# protect.net
KiCad netlist of a schematic drawn in Altium Designer
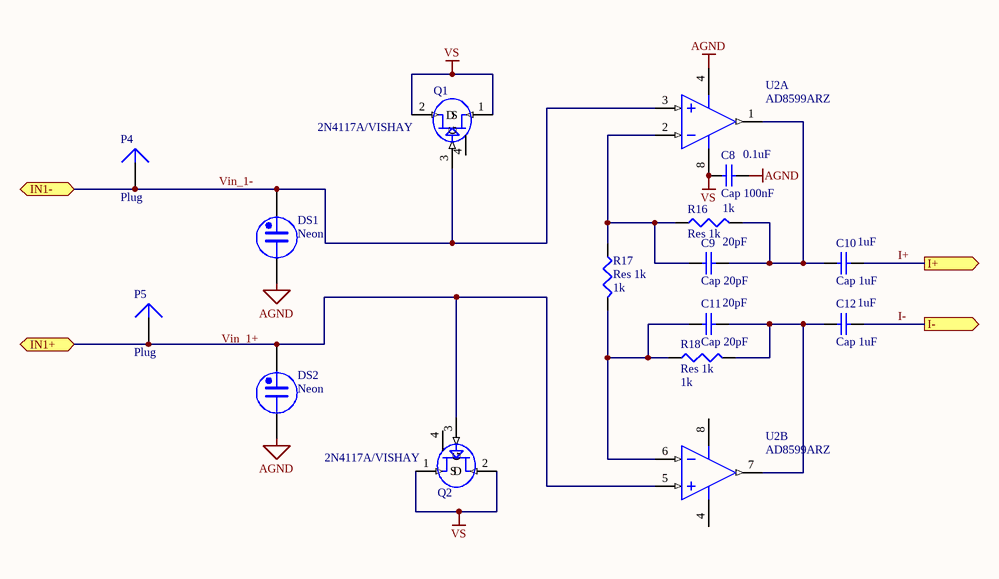
[diagram p0: protect.SchDoc]

(export (version "E")
  (design (tool "Eeschema 10.0.6"))
  (components
    (comp (ref "C8")
      (value "Cap 100nF")
      (footprint "0402")
      (description "Capacitor (Semiconductor SIM Model)")
      (fields (field (name "ALTIUM_VALUE") "0.1uF") (field (name "PUBLISHER") "Altium Limited"))
      (libsource (lib "Miscellaneous Devices") (part "Cap Semi"))
    )
    (comp (ref "C9")
      (value "Cap 20pF")
      (footprint "0402")
      (description "Capacitor (Semiconductor SIM Model)")
      (fields (field (name "ALTIUM_VALUE") "20pF") (field (name "PUBLISHER") "Altium Limited"))
      (libsource (lib "Miscellaneous Devices") (part "Cap Semi"))
    )
    (comp (ref "C10")
      (value "Cap 1uF")
      (footprint "0402")
      (description "Capacitor (Semiconductor SIM Model)")
      (fields (field (name "ALTIUM_VALUE") "1uF") (field (name "PUBLISHER") "Altium Limited"))
      (libsource (lib "Miscellaneous Devices") (part "Cap Semi"))
    )
    (comp (ref "C11")
      (value "Cap 20pF")
      (footprint "0402")
      (description "Capacitor (Semiconductor SIM Model)")
      (fields (field (name "ALTIUM_VALUE") "20pF") (field (name "PUBLISHER") "Altium Limited"))
      (libsource (lib "Miscellaneous Devices") (part "Cap Semi"))
    )
    (comp (ref "C12")
      (value "Cap 1uF")
      (footprint "0402")
      (description "Capacitor (Semiconductor SIM Model)")
      (fields (field (name "ALTIUM_VALUE") "1uF") (field (name "PUBLISHER") "Altium Limited"))
      (libsource (lib "Miscellaneous Devices") (part "Cap Semi"))
    )
    (comp (ref "DS1")
      (value "Neon")
      (footprint "PIN2")
      (description "Neon Bulb")
      (fields (field (name "PUBLISHER") "Altium Limited"))
      (libsource (lib "Miscellaneous Devices") (part "Neon"))
    )
    (comp (ref "DS2")
      (value "Neon")
      (footprint "PIN2")
      (description "Neon Bulb")
      (fields (field (name "PUBLISHER") "Altium Limited"))
      (libsource (lib "Miscellaneous Devices") (part "Neon"))
    )
    (comp (ref "P4")
      (value "Plug")
      (footprint "PIN1")
      (fields (field (name "PUBLISHER") "Altium Limited"))
      (libsource (lib "Miscellaneous Connectors") (part "Plug"))
    )
    (comp (ref "P5")
      (value "Plug")
      (footprint "PIN1")
      (fields (field (name "PUBLISHER") "Altium Limited"))
      (libsource (lib "Miscellaneous Connectors") (part "Plug"))
    )
    (comp (ref "Q1") (value "2N4117A/VISHAY") (footprint "TO236") (libsource (lib "*") (part "JFET N")))
    (comp (ref "Q2") (value "2N4117A/VISHAY") (footprint "TO236") (libsource (lib "*") (part "JFET N")))
    (comp (ref "R16")
      (value "Res 1k")
      (footprint "0402")
      (description "Resistor")
      (fields (field (name "ALTIUM_VALUE") "1k") (field (name "PUBLISHER") "Altium Limited"))
      (libsource (lib "Miscellaneous Devices") (part "Res3"))
    )
    (comp (ref "R17")
      (value "Res 1k")
      (footprint "0402")
      (description "Resistor")
      (fields (field (name "ALTIUM_VALUE") "1k") (field (name "PUBLISHER") "Altium Limited"))
      (libsource (lib "Miscellaneous Devices") (part "Res3"))
    )
    (comp (ref "R18")
      (value "Res 1k")
      (footprint "0402")
      (description "Resistor")
      (fields (field (name "ALTIUM_VALUE") "1k") (field (name "PUBLISHER") "Altium Limited"))
      (libsource (lib "Miscellaneous Devices") (part "Res3"))
    )
    (comp (ref "U2")
      (value "AD8599ARZ")
      (footprint "ADI-R-8_N")
      (fields (field (name "GENERICA PART NUMBER") "AD8599") (field (name "MANUFACTURER") "Analog Devices"))
      (libsource (lib "Analog Devices Operational Amplifiers") (part "AD8599ARZ"))
    )
  )
  (nets
    (net (code "1") (name "/I+") (class "Default")
      (node (ref "C10") (pin "1") (pinfunction "1_1") (pintype "passive"))
    )
    (net (code "2") (name "/I-") (class "Default")
      (node (ref "C12") (pin "1") (pinfunction "1_1") (pintype "passive"))
    )
    (net (code "3") (name "/IN1+") (class "Default")
      (node (ref "DS2") (pin "1") (pinfunction "1_1") (pintype "passive"))
      (node (ref "P5") (pin "1") (pinfunction "1_1") (pintype "passive"))
      (node (ref "Q2") (pin "3") (pinfunction "G_3") (pintype "input"))
      (node (ref "U2") (pin "5") (pinfunction "+IN_B_5") (pintype "input"))
    )
    (net (code "5") (name "/Vin_1-") (class "Default")
      (node (ref "DS1") (pin "1") (pinfunction "1_1") (pintype "passive"))
      (node (ref "P4") (pin "1") (pinfunction "1_1") (pintype "passive"))
      (node (ref "Q1") (pin "3") (pinfunction "G_3") (pintype "input"))
      (node (ref "U2") (pin "3") (pinfunction "+IN_A_3") (pintype "input"))
    )
    (net (code "6") (name "AGND") (class "Default")
      (node (ref "C8") (pin "1") (pinfunction "1_1") (pintype "passive"))
      (node (ref "DS1") (pin "2") (pinfunction "2_2") (pintype "passive"))
      (node (ref "DS2") (pin "2") (pinfunction "2_2") (pintype "passive"))
      (node (ref "U2") (pin "4") (pinfunction "-V_4") (pintype "power_in"))
    )
    (net (code "7") (name "Net-(U2A--IN_A)") (class "Default")
      (node (ref "C9") (pin "2") (pinfunction "2_2") (pintype "passive"))
      (node (ref "R16") (pin "1") (pinfunction "1_1") (pintype "passive"))
      (node (ref "R17") (pin "1") (pinfunction "1_1") (pintype "passive"))
      (node (ref "U2") (pin "2") (pinfunction "-IN_A_2") (pintype "input"))
    )
    (net (code "8") (name "Net-(U2A-OUT_A)") (class "Default")
      (node (ref "C10") (pin "2") (pinfunction "2_2") (pintype "passive"))
      (node (ref "C9") (pin "1") (pinfunction "1_1") (pintype "passive"))
      (node (ref "R16") (pin "2") (pinfunction "2_2") (pintype "passive"))
      (node (ref "U2") (pin "1") (pinfunction "OUT_A_1") (pintype "output"))
    )
    (net (code "9") (name "Net-(U2B--IN_B)") (class "Default")
      (node (ref "C11") (pin "2") (pinfunction "2_2") (pintype "passive"))
      (node (ref "R17") (pin "2") (pinfunction "2_2") (pintype "passive"))
      (node (ref "R18") (pin "1") (pinfunction "1_1") (pintype "passive"))
      (node (ref "U2") (pin "6") (pinfunction "-IN_B_6") (pintype "input"))
    )
    (net (code "10") (name "Net-(U2B-OUT_B)") (class "Default")
      (node (ref "C11") (pin "1") (pinfunction "1_1") (pintype "passive"))
      (node (ref "C12") (pin "2") (pinfunction "2_2") (pintype "passive"))
      (node (ref "R18") (pin "2") (pinfunction "2_2") (pintype "passive"))
      (node (ref "U2") (pin "7") (pinfunction "OUT_B_7") (pintype "output"))
    )
    (net (code "11") (name "VS") (class "Default")
      (node (ref "C8") (pin "2") (pinfunction "2_2") (pintype "passive"))
      (node (ref "Q1") (pin "1") (pinfunction "S_1") (pintype "input"))
      (node (ref "Q1") (pin "2") (pinfunction "D_2") (pintype "input"))
      (node (ref "Q2") (pin "1") (pinfunction "S_1") (pintype "input"))
      (node (ref "Q2") (pin "2") (pinfunction "D_2") (pintype "input"))
      (node (ref "U2") (pin "8") (pinfunction "+V_8") (pintype "power_in"))
    )
    (net (code "12") (name "unconnected-(Q1-Pad4)") (class "Default")
      (node (ref "Q1") (pin "4") (pintype "passive"))
    )
    (net (code "13") (name "unconnected-(Q2-Pad4)") (class "Default")
      (node (ref "Q2") (pin "4") (pintype "passive"))
    )
    (net (code "14") (name "unconnected-(U2B-+V-Pad8)") (class "Default")
      (node (ref "U2") (pin "8") (pinfunction "+V_8") (pintype "power_in"))
    )
    (net (code "15") (name "unconnected-(U2B--V-Pad4)") (class "Default")
      (node (ref "U2") (pin "4") (pinfunction "-V_4") (pintype "power_in"))
    )
  )
)
